# LoRa-module.net
KiCad netlist of a schematic drawn in Altium Designer
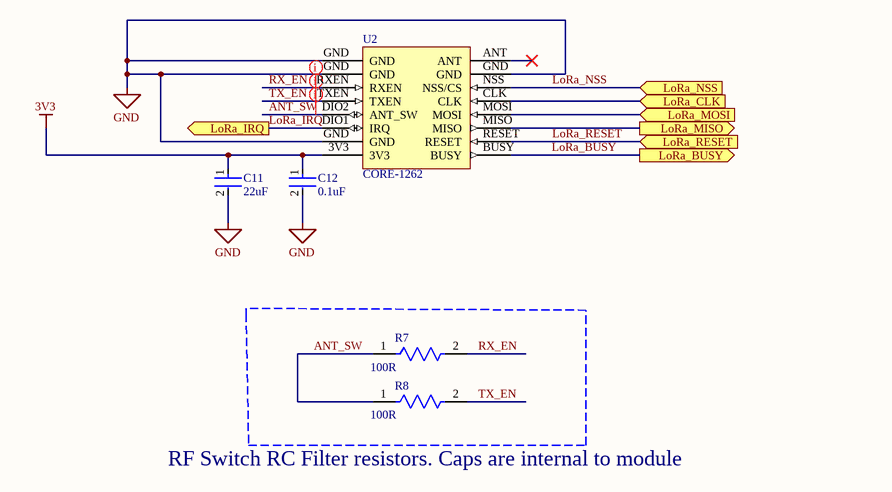
[diagram p0: LoRa-module.SchDoc]

(export (version "E")
  (design (tool "Eeschema 10.0.6"))
  (components
    (comp (ref "C11")
      (value "22uF")
      (footprint "FP-GRM21B-0_15-MFG")
      (description "Chip Multilayer Ceramic Capacitors for General Purpose, 0805, 22uF, X5R, 15%, 20%, 6.3V")
      (fields (field (name "VOLTAGE") "6.3V") (field (name "TOLERANCE") "20%"))
      (libsource (lib "Altium Content Vault") (part "b4654b650e69147ec39a6b967a45e02"))
    )
    (comp (ref "C12")
      (value "0.1uF")
      (footprint "FP-GCM21B-0_15-MFG")
      (description "Ceramic Capacitor for Automotive 100nF ±10% 100VDC X7R 0805 Embossed T/R")
      (fields (field (name "TOLERANCE") "10%") (field (name "VOLTAGE") "100V"))
      (libsource (lib "Altium Content Vault") (part "02cd4be3c70576c341d710602a673aa"))
    )
    (comp (ref "R7")
      (value "RMCF0805FT100R")
      (footprint "FP-RMCF0805-IPC_A")
      (description "100Ω ±1% 0.125W 0805 Thick Film Chip Resistor AEC-Q200 compliant")
      (fields (field (name "TOLERANCE") "1%") (field (name "RESISTANCE") "100R"))
      (libsource (lib "Altium Content Vault") (part "1029c3af85768c4190bb7ad29bc67b5"))
    )
    (comp (ref "R8")
      (value "RMCF0805FT100R")
      (footprint "FP-RMCF0805-IPC_A")
      (description "100Ω ±1% 0.125W 0805 Thick Film Chip Resistor AEC-Q200 compliant")
      (fields (field (name "TOLERANCE") "1%") (field (name "RESISTANCE") "100R"))
      (libsource (lib "Altium Content Vault") (part "1029c3af85768c4190bb7ad29bc67b5"))
    )
    (comp (ref "U2")
      (value "CORE-1262")
      (footprint "WAVE-20855-Core1262")
      (description "LoRa HF module")
      (libsource (lib "Core1262") (part "CORE-1262"))
    )
  )
  (nets
    (net (code "1") (name "/ANT_SW") (class "Default")
      (node (ref "R7") (pin "1") (pinfunction "1_1") (pintype "passive"))
      (node (ref "R8") (pin "1") (pinfunction "1_1") (pintype "passive"))
      (node (ref "U2") (pin "DIO2") (pinfunction "ANT_SW_DIO2") (pintype "bidirectional"))
    )
    (net (code "2") (name "/LoRa_BUSY") (class "Default")
      (node (ref "U2") (pin "BUSY") (pinfunction "BUSY_BUSY") (pintype "output"))
    )
    (net (code "3") (name "/LoRa_CLK") (class "Default")
      (node (ref "U2") (pin "CLK") (pinfunction "CLK_CLK") (pintype "input"))
    )
    (net (code "4") (name "/LoRa_IRQ") (class "Default")
      (node (ref "U2") (pin "DIO1") (pinfunction "IRQ_DIO1") (pintype "bidirectional"))
    )
    (net (code "5") (name "/LoRa_MISO") (class "Default")
      (node (ref "U2") (pin "MISO") (pinfunction "MISO_MISO") (pintype "output"))
    )
    (net (code "6") (name "/LoRa_MOSI") (class "Default")
      (node (ref "U2") (pin "MOSI") (pinfunction "MOSI_MOSI") (pintype "input"))
    )
    (net (code "7") (name "/LoRa_NSS") (class "Default")
      (node (ref "U2") (pin "NSS") (pinfunction "NSS/CS_NSS") (pintype "input"))
    )
    (net (code "8") (name "/LoRa_RESET") (class "Default")
      (node (ref "U2") (pin "RESET") (pinfunction "RESET_RESET") (pintype "input"))
    )
    (net (code "9") (name "/RX_EN") (class "Default")
      (node (ref "R7") (pin "2") (pinfunction "2_2") (pintype "passive"))
      (node (ref "U2") (pin "RXEN") (pinfunction "RXEN_RXEN") (pintype "input"))
    )
    (net (code "10") (name "/TX_EN") (class "Default")
      (node (ref "R8") (pin "2") (pinfunction "2_2") (pintype "passive"))
      (node (ref "U2") (pin "TXEN") (pinfunction "TXEN_TXEN") (pintype "input"))
    )
    (net (code "11") (name "3V3") (class "Default")
      (node (ref "C11") (pin "1") (pinfunction "1_1") (pintype "passive"))
      (node (ref "C12") (pin "1") (pinfunction "1_1") (pintype "passive"))
      (node (ref "U2") (pin "3V3") (pinfunction "3V3_3V3") (pintype "power_in"))
    )
    (net (code "12") (name "GND") (class "Default")
      (node (ref "C11") (pin "2") (pinfunction "2_2") (pintype "passive"))
      (node (ref "C12") (pin "2") (pinfunction "2_2") (pintype "passive"))
      (node (ref "U2") (pin "GND") (pinfunction "GND_GND") (pintype "power_in"))
    )
    (net (code "13") (name "unconnected-(U2-PadANT)") (class "Default")
      (node (ref "U2") (pin "ANT") (pinfunction "ANT_ANT") (pintype "passive"))
    )
    (net (code "14") (name "unconnected-(U2-PadGND)") (class "Default")
      (node (ref "U2") (pin "GND") (pinfunction "GND_GND") (pintype "power_in"))
    )
  )
)
